# wsbd_v2.net
KiCad netlist of a schematic drawn in EAGLE
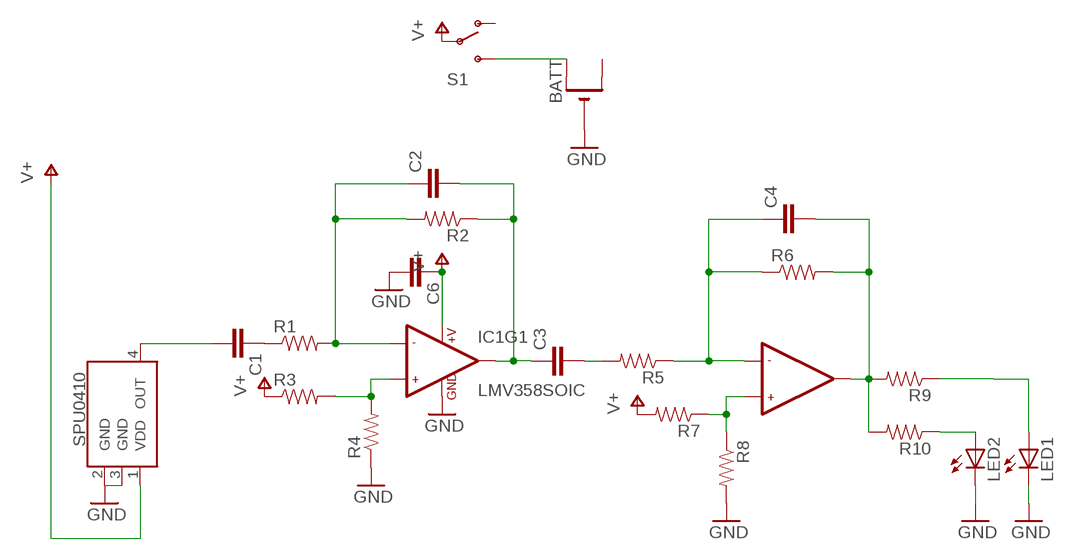
[diagram p0: schematic, sheet 1]

(export (version "E")
  (design (tool "Eeschema 10.0.6"))
  (components
    (comp (ref "BATT")
      (value "CR2032MPD1")
      (footprint "eagle-import:CR2032-THRU")
      (libsource (lib "eagle-import") (part "CR2032MPD1"))
    )
    (comp (ref "C1")
      (value "CAP0805")
      (footprint "eagle-import:0805")
      (libsource (lib "eagle-import") (part "CAP0805"))
    )
    (comp (ref "C2")
      (value "CAP0805")
      (footprint "eagle-import:0805")
      (libsource (lib "eagle-import") (part "CAP0805"))
    )
    (comp (ref "C3")
      (value "CAP0805")
      (footprint "eagle-import:0805")
      (libsource (lib "eagle-import") (part "CAP0805"))
    )
    (comp (ref "C4")
      (value "CAP0805")
      (footprint "eagle-import:0805")
      (libsource (lib "eagle-import") (part "CAP0805"))
    )
    (comp (ref "C6")
      (value "CAP0805")
      (footprint "eagle-import:0805")
      (libsource (lib "eagle-import") (part "CAP0805"))
    )
    (comp (ref "IC1")
      (value "LMV358SOIC")
      (footprint "eagle-import:SO08")
      (libsource (lib "eagle-import") (part "LMV358SOIC"))
    )
    (comp (ref "LED1")
      (value "LEDCHIP-LED0805")
      (footprint "eagle-import:CHIP-LED0805")
      (libsource (lib "eagle-import") (part "LEDCHIP-LED0805"))
    )
    (comp (ref "LED2")
      (value "LEDCHIP-LED0805")
      (footprint "eagle-import:CHIP-LED0805")
      (libsource (lib "eagle-import") (part "LEDCHIP-LED0805"))
    )
    (comp (ref "R1")
      (value "RESISTOR0805-RES")
      (footprint "eagle-import:0805")
      (libsource (lib "eagle-import") (part "RESISTOR0805-RES"))
    )
    (comp (ref "R2")
      (value "RESISTOR0805-RES")
      (footprint "eagle-import:0805")
      (libsource (lib "eagle-import") (part "RESISTOR0805-RES"))
    )
    (comp (ref "R3")
      (value "RESISTOR0805-RES")
      (footprint "eagle-import:0805")
      (libsource (lib "eagle-import") (part "RESISTOR0805-RES"))
    )
    (comp (ref "R4")
      (value "RESISTOR0805-RES")
      (footprint "eagle-import:0805")
      (libsource (lib "eagle-import") (part "RESISTOR0805-RES"))
    )
    (comp (ref "R5")
      (value "RESISTOR0805-RES")
      (footprint "eagle-import:0805")
      (libsource (lib "eagle-import") (part "RESISTOR0805-RES"))
    )
    (comp (ref "R6")
      (value "RESISTOR0805-RES")
      (footprint "eagle-import:0805")
      (libsource (lib "eagle-import") (part "RESISTOR0805-RES"))
    )
    (comp (ref "R7")
      (value "RESISTOR0805-RES")
      (footprint "eagle-import:0805")
      (libsource (lib "eagle-import") (part "RESISTOR0805-RES"))
    )
    (comp (ref "R8")
      (value "RESISTOR0805-RES")
      (footprint "eagle-import:0805")
      (libsource (lib "eagle-import") (part "RESISTOR0805-RES"))
    )
    (comp (ref "R9")
      (value "RESISTOR0805-RES")
      (footprint "eagle-import:0805")
      (libsource (lib "eagle-import") (part "RESISTOR0805-RES"))
    )
    (comp (ref "R10")
      (value "RESISTOR0805-RES")
      (footprint "eagle-import:0805")
      (libsource (lib "eagle-import") (part "RESISTOR0805-RES"))
    )
    (comp (ref "S1")
      (value "SWITCH-SPDT-SMD-A")
      (footprint "eagle-import:SWITCH-SPST-SMD-A")
      (libsource (lib "eagle-import") (part "SWITCH-SPDT-SMD-A"))
    )
    (comp (ref "U$1")
      (value "SPU0410")
      (footprint "eagle-import:SPSERIES1")
      (libsource (lib "eagle-import") (part "SPU0410"))
    )
  )
  (nets
    (net (code "1") (name "GND") (class "Default")
      (node (ref "BATT") (pin "GND") (pinfunction "-_GND") (pintype "passive"))
      (node (ref "C6") (pin "2") (pinfunction "2_2") (pintype "passive"))
      (node (ref "IC1") (pin "4") (pinfunction "GND_4") (pintype "power_in"))
      (node (ref "LED1") (pin "C") (pinfunction "C_C") (pintype "passive"))
      (node (ref "LED2") (pin "C") (pinfunction "C_C") (pintype "passive"))
      (node (ref "R4") (pin "1") (pinfunction "1_1") (pintype "passive"))
      (node (ref "R8") (pin "2") (pinfunction "2_2") (pintype "passive"))
      (node (ref "U$1") (pin "2") (pinfunction "GND_2") (pintype "bidirectional"))
      (node (ref "U$1") (pin "3") (pinfunction "GND_3") (pintype "bidirectional"))
    )
    (net (code "2") (name "Net-(BATT-+)") (class "Default")
      (node (ref "BATT") (pin "+1") (pinfunction "+_+1") (pintype "passive"))
      (node (ref "S1") (pin "3") (pinfunction "S_3") (pintype "passive"))
    )
    (net (code "3") (name "Net-(C1-Pad1)") (class "Default")
      (node (ref "C1") (pin "1") (pinfunction "1_1") (pintype "passive"))
      (node (ref "R1") (pin "1") (pinfunction "1_1") (pintype "passive"))
    )
    (net (code "4") (name "Net-(C3-Pad2)") (class "Default")
      (node (ref "C3") (pin "2") (pinfunction "2_2") (pintype "passive"))
      (node (ref "R5") (pin "2") (pinfunction "2_2") (pintype "passive"))
    )
    (net (code "5") (name "Net-(IC1A-+IN1)") (class "Default")
      (node (ref "IC1") (pin "3") (pinfunction "+IN1_3") (pintype "input"))
      (node (ref "R3") (pin "2") (pinfunction "2_2") (pintype "passive"))
      (node (ref "R4") (pin "2") (pinfunction "2_2") (pintype "passive"))
    )
    (net (code "6") (name "Net-(IC1A--IN1)") (class "Default")
      (node (ref "C2") (pin "1") (pinfunction "1_1") (pintype "passive"))
      (node (ref "IC1") (pin "2") (pinfunction "-IN1_2") (pintype "input"))
      (node (ref "R1") (pin "2") (pinfunction "2_2") (pintype "passive"))
      (node (ref "R2") (pin "2") (pinfunction "2_2") (pintype "passive"))
    )
    (net (code "7") (name "Net-(IC1A-OUT1)") (class "Default")
      (node (ref "C2") (pin "2") (pinfunction "2_2") (pintype "passive"))
      (node (ref "C3") (pin "1") (pinfunction "1_1") (pintype "passive"))
      (node (ref "IC1") (pin "1") (pinfunction "OUT1_1") (pintype "output"))
      (node (ref "R2") (pin "1") (pinfunction "1_1") (pintype "passive"))
    )
    (net (code "8") (name "Net-(IC1B-+IN2)") (class "Default")
      (node (ref "IC1") (pin "5") (pinfunction "+IN2_5") (pintype "input"))
      (node (ref "R7") (pin "1") (pinfunction "1_1") (pintype "passive"))
      (node (ref "R8") (pin "1") (pinfunction "1_1") (pintype "passive"))
    )
    (net (code "9") (name "Net-(IC1B--IN2)") (class "Default")
      (node (ref "C4") (pin "1") (pinfunction "1_1") (pintype "passive"))
      (node (ref "IC1") (pin "6") (pinfunction "-IN2_6") (pintype "input"))
      (node (ref "R5") (pin "1") (pinfunction "1_1") (pintype "passive"))
      (node (ref "R6") (pin "1") (pinfunction "1_1") (pintype "passive"))
    )
    (net (code "10") (name "Net-(IC1B-OUT2)") (class "Default")
      (node (ref "C4") (pin "2") (pinfunction "2_2") (pintype "passive"))
      (node (ref "IC1") (pin "7") (pinfunction "OUT2_7") (pintype "output"))
      (node (ref "R10") (pin "2") (pinfunction "2_2") (pintype "passive"))
      (node (ref "R6") (pin "2") (pinfunction "2_2") (pintype "passive"))
      (node (ref "R9") (pin "2") (pinfunction "2_2") (pintype "passive"))
    )
    (net (code "11") (name "Net-(LED1-PadA)") (class "Default")
      (node (ref "LED1") (pin "A") (pinfunction "A_A") (pintype "passive"))
      (node (ref "R9") (pin "1") (pinfunction "1_1") (pintype "passive"))
    )
    (net (code "12") (name "Net-(LED2-PadA)") (class "Default")
      (node (ref "LED2") (pin "A") (pinfunction "A_A") (pintype "passive"))
      (node (ref "R10") (pin "1") (pinfunction "1_1") (pintype "passive"))
    )
    (net (code "13") (name "Net-(U$1-OUT)") (class "Default")
      (node (ref "C1") (pin "2") (pinfunction "2_2") (pintype "passive"))
      (node (ref "U$1") (pin "4") (pinfunction "OUT_4") (pintype "bidirectional"))
    )
    (net (code "14") (name "V+") (class "Default")
      (node (ref "C6") (pin "1") (pinfunction "1_1") (pintype "passive"))
      (node (ref "IC1") (pin "8") (pinfunction "+V_8") (pintype "power_in"))
      (node (ref "R3") (pin "1") (pinfunction "1_1") (pintype "passive"))
      (node (ref "R7") (pin "2") (pinfunction "2_2") (pintype "passive"))
      (node (ref "S1") (pin "2") (pinfunction "P_2") (pintype "passive"))
      (node (ref "U$1") (pin "1") (pinfunction "VDD_1") (pintype "bidirectional"))
    )
    (net (code "15") (name "unconnected-(BATT-+1-Pad+2)") (class "Default")
      (node (ref "BATT") (pin "+2") (pinfunction "+1_+2") (pintype "passive"))
    )
    (net (code "16") (name "unconnected-(S1-O-Pad1)") (class "Default")
      (node (ref "S1") (pin "1") (pinfunction "O_1") (pintype "passive"))
    )
  )
)
